# npm1300_qeaa_config1.net
KiCad netlist of a schematic drawn in Altium Designer
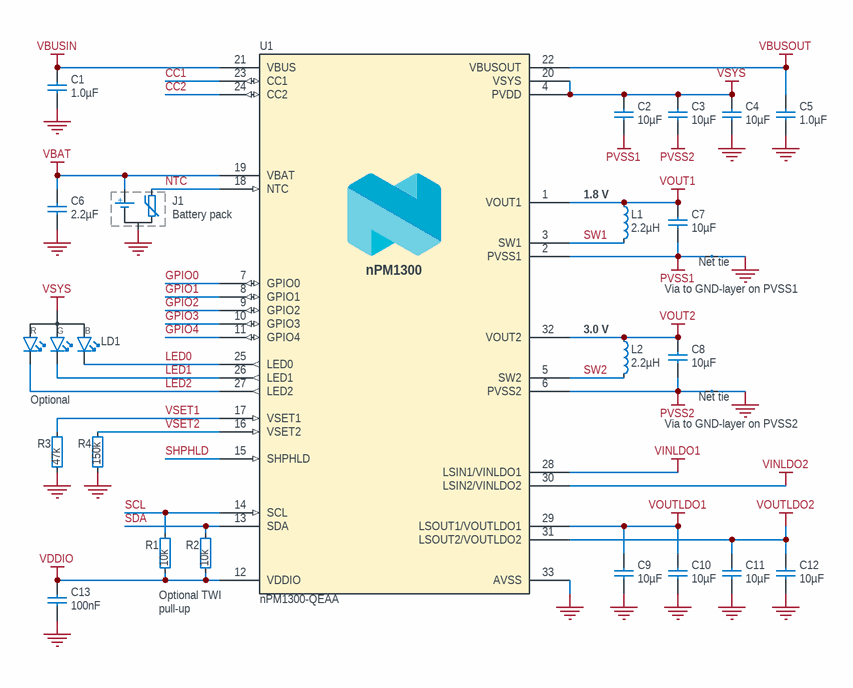
[diagram p0: npm1300_qeaa_config1.SchDoc]

(export (version "E")
  (design (tool "Eeschema 10.0.6"))
  (components
    (comp (ref "C1")
      (value "1.0µF")
      (footprint "CAPC1608X06L")
      (description "Capacitor, Ceramic, 1.0µF 10V X5R 0603,±10%")
      (fields
        (field (name "PART NUMBER") "C0603-1µ0-10V-X5R")
        (field (name "MANUFACTURER") "N.A.")
        (field (name "AUTHOR") "getr")
      )
      (libsource (lib "AltiumLib") (part "CAP"))
    )
    (comp (ref "C2")
      (value "10µF")
      (footprint "CAPC1608X06L")
      (description "Capacitor, X5R, ±20%")
      (fields
        (field (name "PART NUMBER") "C0603-10µ")
        (field (name "MANUFACTURER") "N.A.")
        (field (name "AUTHOR") "rsk")
      )
      (libsource (lib "AltiumLib") (part "CAP"))
    )
    (comp (ref "C3")
      (value "10µF")
      (footprint "CAPC1608X06L")
      (description "Capacitor, X5R, ±20%")
      (fields
        (field (name "PART NUMBER") "C0603-10µ")
        (field (name "MANUFACTURER") "N.A.")
        (field (name "AUTHOR") "rsk")
      )
      (libsource (lib "AltiumLib") (part "CAP"))
    )
    (comp (ref "C4")
      (value "10µF")
      (footprint "CAPC1608X06L")
      (description "Capacitor, X5R, ±20%")
      (fields
        (field (name "PART NUMBER") "C0603-10µ")
        (field (name "MANUFACTURER") "N.A.")
        (field (name "AUTHOR") "rsk")
      )
      (libsource (lib "AltiumLib") (part "CAP"))
    )
    (comp (ref "C5")
      (value "1.0µF")
      (footprint "CAPC1608X06L")
      (description "Capacitor, Ceramic, 1.0µF 10V X5R 0603,±10%")
      (fields
        (field (name "PART NUMBER") "C0603-1µ0-10V-X5R")
        (field (name "MANUFACTURER") "N.A.")
        (field (name "AUTHOR") "getr")
      )
      (libsource (lib "AltiumLib") (part "CAP"))
    )
    (comp (ref "C6")
      (value "2.2µF")
      (footprint "CAPC1608X06L")
      (description "Capacitor, Ceramic, X7R, ±10%, 16V")
      (fields
        (field (name "PART NUMBER") "C0603-2.2µ-16V-X7R")
        (field (name "MANUFACTURER") "Taiyo Yuden")
        (field (name "AUTHOR") "rsk")
      )
      (libsource (lib "AltiumLib") (part "CAP"))
    )
    (comp (ref "C7")
      (value "10µF")
      (footprint "CAPC1608X06L")
      (description "Capacitor, X5R, ±20%")
      (fields
        (field (name "PART NUMBER") "C0603-10µ")
        (field (name "MANUFACTURER") "N.A.")
        (field (name "AUTHOR") "rsk")
      )
      (libsource (lib "AltiumLib") (part "CAP"))
    )
    (comp (ref "C8")
      (value "10µF")
      (footprint "CAPC1608X06L")
      (description "Capacitor, X5R, ±20%")
      (fields
        (field (name "PART NUMBER") "C0603-10µ")
        (field (name "MANUFACTURER") "N.A.")
        (field (name "AUTHOR") "rsk")
      )
      (libsource (lib "AltiumLib") (part "CAP"))
    )
    (comp (ref "C9")
      (value "10µF")
      (footprint "CAPC1608X06L")
      (description "Capacitor, X5R, ±20%")
      (fields
        (field (name "PART NUMBER") "C0603-10µ")
        (field (name "MANUFACTURER") "N.A.")
        (field (name "AUTHOR") "rsk")
      )
      (libsource (lib "AltiumLib") (part "CAP"))
    )
    (comp (ref "C10")
      (value "10µF")
      (footprint "CAPC1608X06L")
      (description "Capacitor, X5R, ±20%")
      (fields
        (field (name "PART NUMBER") "C0603-10µ")
        (field (name "MANUFACTURER") "N.A.")
        (field (name "AUTHOR") "rsk")
      )
      (libsource (lib "AltiumLib") (part "CAP"))
    )
    (comp (ref "C11")
      (value "10µF")
      (footprint "CAPC1608X06L")
      (description "Capacitor, X5R, ±20%")
      (fields
        (field (name "PART NUMBER") "C0603-10µ")
        (field (name "MANUFACTURER") "N.A.")
        (field (name "AUTHOR") "rsk")
      )
      (libsource (lib "AltiumLib") (part "CAP"))
    )
    (comp (ref "C12")
      (value "10µF")
      (footprint "CAPC1608X06L")
      (description "Capacitor, X5R, ±20%")
      (fields
        (field (name "PART NUMBER") "C0603-10µ")
        (field (name "MANUFACTURER") "N.A.")
        (field (name "AUTHOR") "rsk")
      )
      (libsource (lib "AltiumLib") (part "CAP"))
    )
    (comp (ref "C13")
      (value "100nF")
      (footprint "CAPC0603X03L_C")
      (description "Capacitor, X5R, ±10%, 100nF, 16V")
      (fields
        (field (name "PART NUMBER") "C0201-100n")
        (field (name "MANUFACTURER") "N.A.")
        (field (name "AUTHOR") "rsk")
      )
      (libsource (lib "AltiumLib") (part "CAP"))
    )
    (comp (ref "J1")
      (value "Battery pack")
      (footprint "TP_3x1mm_TH")
      (description "Battery pack with NTC")
      (fields
        (field (name "PART NUMBER") "Battery_w/NTC_TP")
        (field (name "MANUFACTURER") "N.A.")
        (field (name "AUTHOR") "rsk")
      )
      (libsource (lib "AltiumLib") (part "Battery_pack_NTC"))
    )
    (comp (ref "L1")
      (value "2.2µH")
      (footprint "INDC2016X10N")
      (description "Inductor, Irms=2.5A, Isat=2.9A, ±20%, DCR=73mΩ")
      (fields
        (field (name "PART NUMBER") "L0806-2µ2-2500mA-73mOhm-CIGT201610EH2R2MNE")
        (field (name "MANUFACTURER") "Samsung Electro-Mechanics America")
        (field (name "AUTHOR") "rsk")
      )
      (libsource (lib "AltiumLib") (part "IND"))
    )
    (comp (ref "L2")
      (value "2.2µH")
      (footprint "INDC2016X10N")
      (description "Inductor, Irms=2.5A, Isat=2.9A, ±20%, DCR=73mΩ")
      (fields
        (field (name "PART NUMBER") "L0806-2µ2-2500mA-73mOhm-CIGT201610EH2R2MNE")
        (field (name "MANUFACTURER") "Samsung Electro-Mechanics America")
        (field (name "AUTHOR") "rsk")
      )
      (libsource (lib "AltiumLib") (part "IND"))
    )
    (comp (ref "LD1")
      (value "LED RGB")
      (footprint "LED_RGB_0603")
      (description "RGB LED 1.60 mm x 0.80 mm SMD")
      (fields
        (field (name "PART NUMBER") "APHF1608LSEEQBDZGKC")
        (field (name "MANUFACTURER") "Kingbright Company LLC")
        (field (name "AUTHOR") "rsk")
      )
      (libsource (lib "AltiumLib") (part "D{colon}LED_RGB"))
    )
    (comp (ref "NT1")
      (value "Net tie")
      (footprint "2 PIN STARPOINT")
      (description "Starpoint")
      (fields
        (field (name "PART NUMBER") "2 pin starpoint")
        (field (name "MANUFACTURER") "N.A.")
        (field (name "AUTHOR") "rsk")
      )
      (libsource (lib "AltiumLib") (part "2 pin starpoint"))
    )
    (comp (ref "NT2")
      (value "Net tie")
      (footprint "2 PIN STARPOINT")
      (description "Starpoint")
      (fields
        (field (name "PART NUMBER") "2 pin starpoint")
        (field (name "MANUFACTURER") "N.A.")
        (field (name "AUTHOR") "rsk")
      )
      (libsource (lib "AltiumLib") (part "2 pin starpoint"))
    )
    (comp (ref "R1")
      (value "10k")
      (footprint "RESC0603X03L_C")
      (description "Resistor, ±1%, 0.05W")
      (fields
        (field (name "PART NUMBER") "R0201-10k")
        (field (name "MANUFACTURER") "N.A.")
        (field (name "AUTHOR") "rsk")
      )
      (libsource (lib "AltiumLib") (part "RES"))
    )
    (comp (ref "R2")
      (value "10k")
      (footprint "RESC0603X03L_C")
      (description "Resistor, ±1%, 0.05W")
      (fields
        (field (name "PART NUMBER") "R0201-10k")
        (field (name "MANUFACTURER") "N.A.")
        (field (name "AUTHOR") "rsk")
      )
      (libsource (lib "AltiumLib") (part "RES"))
    )
    (comp (ref "R3")
      (value "47k")
      (footprint "RESC0603X03L_C")
      (description "Resistor, ±1%, 0.05W")
      (fields
        (field (name "PART NUMBER") "R0201-47k")
        (field (name "MANUFACTURER") "N.A.")
        (field (name "AUTHOR") "rsk")
      )
      (libsource (lib "AltiumLib") (part "RES"))
    )
    (comp (ref "R4")
      (value "150k")
      (footprint "RESC0603X03L_C")
      (description "Resistor, ±1%, 0.05W")
      (fields
        (field (name "PART NUMBER") "R0201-150k")
        (field (name "MANUFACTURER") "N.A.")
        (field (name "AUTHOR") "rsk")
      )
      (libsource (lib "AltiumLib") (part "RES"))
    )
    (comp (ref "U1")
      (value "nPM1300-QEAA")
      (footprint "Nordic_QFN50P500X500X90-33N")
      (fields (field (name "MANUFACTURER") "Nordic Semiconductor") (field (name "AUTHOR") "eisk"))
      (libsource (lib "AltiumLib") (part "nPM1300_QEAA"))
    )
  )
  (nets
    (net (code "1") (name "/CC1") (class "Default")
      (node (ref "U1") (pin "23") (pinfunction "CC1_23") (pintype "bidirectional"))
    )
    (net (code "2") (name "/CC2") (class "Default")
      (node (ref "U1") (pin "24") (pinfunction "CC2_24") (pintype "bidirectional"))
    )
    (net (code "3") (name "/GPIO0") (class "Default")
      (node (ref "U1") (pin "7") (pinfunction "GPIO0_7") (pintype "bidirectional"))
    )
    (net (code "4") (name "/GPIO1") (class "Default")
      (node (ref "U1") (pin "8") (pinfunction "GPIO1_8") (pintype "bidirectional"))
    )
    (net (code "5") (name "/GPIO2") (class "Default")
      (node (ref "U1") (pin "9") (pinfunction "GPIO2_9") (pintype "bidirectional"))
    )
    (net (code "6") (name "/GPIO3") (class "Default")
      (node (ref "U1") (pin "10") (pinfunction "GPIO3_10") (pintype "bidirectional"))
    )
    (net (code "7") (name "/GPIO4") (class "Default")
      (node (ref "U1") (pin "11") (pinfunction "GPIO4_11") (pintype "bidirectional"))
    )
    (net (code "8") (name "/LED0") (class "Default")
      (node (ref "LD1") (pin "3") (pinfunction "C_BLUE_3") (pintype "passive"))
      (node (ref "U1") (pin "25") (pinfunction "LED0_25") (pintype "output"))
    )
    (net (code "9") (name "/LED1") (class "Default")
      (node (ref "LD1") (pin "2") (pinfunction "C_GREEN_2") (pintype "passive"))
      (node (ref "U1") (pin "26") (pinfunction "LED1_26") (pintype "output"))
    )
    (net (code "10") (name "/LED2") (class "Default")
      (node (ref "LD1") (pin "1") (pinfunction "C_RED_1") (pintype "passive"))
      (node (ref "U1") (pin "27") (pinfunction "LED2_27") (pintype "output"))
    )
    (net (code "11") (name "/NTC") (class "Default")
      (node (ref "J1") (pin "2") (pinfunction "NTC_2") (pintype "passive"))
      (node (ref "U1") (pin "18") (pinfunction "NTC_18") (pintype "input"))
    )
    (net (code "12") (name "/SCL") (class "Default")
      (node (ref "R1") (pin "1") (pinfunction "1_1") (pintype "passive"))
      (node (ref "U1") (pin "14") (pinfunction "SCL_14") (pintype "input"))
    )
    (net (code "13") (name "/SDA") (class "Default")
      (node (ref "R2") (pin "1") (pinfunction "1_1") (pintype "passive"))
      (node (ref "U1") (pin "13") (pinfunction "SDA_13") (pintype "open_collector"))
    )
    (net (code "14") (name "/SHPHLD") (class "Default")
      (node (ref "U1") (pin "15") (pinfunction "SHPHLD_15") (pintype "input"))
    )
    (net (code "15") (name "/SW1") (class "Default")
      (node (ref "L1") (pin "2") (pinfunction "2_2") (pintype "passive"))
      (node (ref "U1") (pin "3") (pinfunction "SW1_3") (pintype "power_in"))
    )
    (net (code "16") (name "/SW2") (class "Default")
      (node (ref "L2") (pin "2") (pinfunction "2_2") (pintype "passive"))
      (node (ref "U1") (pin "5") (pinfunction "SW2_5") (pintype "power_in"))
    )
    (net (code "17") (name "/VSET1") (class "Default")
      (node (ref "R3") (pin "1") (pinfunction "1_1") (pintype "passive"))
      (node (ref "U1") (pin "17") (pinfunction "VSET1_17") (pintype "input"))
    )
    (net (code "18") (name "/VSET2") (class "Default")
      (node (ref "R4") (pin "1") (pinfunction "1_1") (pintype "passive"))
      (node (ref "U1") (pin "16") (pinfunction "VSET2_16") (pintype "input"))
    )
    (net (code "19") (name "GND") (class "Default")
      (node (ref "C1") (pin "1") (pinfunction "1_1") (pintype "passive"))
      (node (ref "C10") (pin "1") (pinfunction "1_1") (pintype "passive"))
      (node (ref "C11") (pin "1") (pinfunction "1_1") (pintype "passive"))
      (node (ref "C12") (pin "1") (pinfunction "1_1") (pintype "passive"))
      (node (ref "C13") (pin "2") (pinfunction "2_2") (pintype "passive"))
      (node (ref "C4") (pin "1") (pinfunction "1_1") (pintype "passive"))
      (node (ref "C5") (pin "1") (pinfunction "1_1") (pintype "passive"))
      (node (ref "C6") (pin "1") (pinfunction "1_1") (pintype "passive"))
      (node (ref "C9") (pin "1") (pinfunction "1_1") (pintype "passive"))
      (node (ref "J1") (pin "1") (pinfunction "GND_1") (pintype "passive"))
      (node (ref "NT1") (pin "1") (pintype "passive"))
      (node (ref "NT2") (pin "1") (pintype "passive"))
      (node (ref "R3") (pin "2") (pinfunction "2_2") (pintype "passive"))
      (node (ref "R4") (pin "2") (pinfunction "2_2") (pintype "passive"))
      (node (ref "U1") (pin "33") (pinfunction "AVSS_33") (pintype "power_in"))
    )
    (net (code "20") (name "PVSS1") (class "Default")
      (node (ref "C2") (pin "1") (pinfunction "1_1") (pintype "passive"))
      (node (ref "C7") (pin "1") (pinfunction "1_1") (pintype "passive"))
      (node (ref "NT1") (pin "2") (pintype "passive"))
      (node (ref "U1") (pin "2") (pinfunction "PVSS1_2") (pintype "power_in"))
    )
    (net (code "21") (name "PVSS2") (class "Default")
      (node (ref "C3") (pin "1") (pinfunction "1_1") (pintype "passive"))
      (node (ref "C8") (pin "1") (pinfunction "1_1") (pintype "passive"))
      (node (ref "NT2") (pin "2") (pintype "passive"))
      (node (ref "U1") (pin "6") (pinfunction "PVSS2_6") (pintype "power_in"))
    )
    (net (code "22") (name "VBAT") (class "Default")
      (node (ref "C6") (pin "2") (pinfunction "2_2") (pintype "passive"))
      (node (ref "J1") (pin "3") (pinfunction "V+_3") (pintype "passive"))
      (node (ref "U1") (pin "19") (pinfunction "VBAT_19") (pintype "passive"))
    )
    (net (code "23") (name "VBUSIN") (class "Default")
      (node (ref "C1") (pin "2") (pinfunction "2_2") (pintype "passive"))
      (node (ref "U1") (pin "21") (pinfunction "VBUS_21") (pintype "power_in"))
    )
    (net (code "24") (name "VBUSOUT") (class "Default")
      (node (ref "C5") (pin "2") (pinfunction "2_2") (pintype "passive"))
      (node (ref "U1") (pin "22") (pinfunction "VBUSOUT_22") (pintype "power_in"))
    )
    (net (code "25") (name "VDDIO") (class "Default")
      (node (ref "C13") (pin "1") (pinfunction "1_1") (pintype "passive"))
      (node (ref "R1") (pin "2") (pinfunction "2_2") (pintype "passive"))
      (node (ref "R2") (pin "2") (pinfunction "2_2") (pintype "passive"))
      (node (ref "U1") (pin "12") (pinfunction "VDDIO_12") (pintype "power_in"))
    )
    (net (code "26") (name "VINLDO1") (class "Default")
      (node (ref "U1") (pin "28") (pinfunction "LSIN1/VINLDO1_28") (pintype "power_in"))
    )
    (net (code "27") (name "VINLDO2") (class "Default")
      (node (ref "U1") (pin "30") (pinfunction "LSIN2/VINLDO2_30") (pintype "power_in"))
    )
    (net (code "28") (name "VOUT1") (class "Default")
      (node (ref "C7") (pin "2") (pinfunction "2_2") (pintype "passive"))
      (node (ref "L1") (pin "1") (pinfunction "1_1") (pintype "passive"))
      (node (ref "U1") (pin "1") (pinfunction "VOUT1_1") (pintype "power_in"))
    )
    (net (code "29") (name "VOUT2") (class "Default")
      (node (ref "C8") (pin "2") (pinfunction "2_2") (pintype "passive"))
      (node (ref "L2") (pin "1") (pinfunction "1_1") (pintype "passive"))
      (node (ref "U1") (pin "32") (pinfunction "VOUT2_32") (pintype "power_in"))
    )
    (net (code "30") (name "VOUTLDO1") (class "Default")
      (node (ref "C10") (pin "2") (pinfunction "2_2") (pintype "passive"))
      (node (ref "C9") (pin "2") (pinfunction "2_2") (pintype "passive"))
      (node (ref "U1") (pin "29") (pinfunction "LSOUT1/VOUTLDO1_29") (pintype "power_in"))
    )
    (net (code "31") (name "VOUTLDO2") (class "Default")
      (node (ref "C11") (pin "2") (pinfunction "2_2") (pintype "passive"))
      (node (ref "C12") (pin "2") (pinfunction "2_2") (pintype "passive"))
      (node (ref "U1") (pin "31") (pinfunction "LSOUT2/VOUTLDO2_31") (pintype "power_in"))
    )
    (net (code "32") (name "VSYS") (class "Default")
      (node (ref "C2") (pin "2") (pinfunction "2_2") (pintype "passive"))
      (node (ref "C3") (pin "2") (pinfunction "2_2") (pintype "passive"))
      (node (ref "C4") (pin "2") (pinfunction "2_2") (pintype "passive"))
      (node (ref "LD1") (pin "4") (pinfunction "A_4") (pintype "passive"))
      (node (ref "U1") (pin "20") (pinfunction "VSYS_20") (pintype "power_in"))
      (node (ref "U1") (pin "4") (pinfunction "PVDD_4") (pintype "power_in"))
    )
  )
)
